# charger.net
KiCad netlist of a schematic drawn in Altium Designer
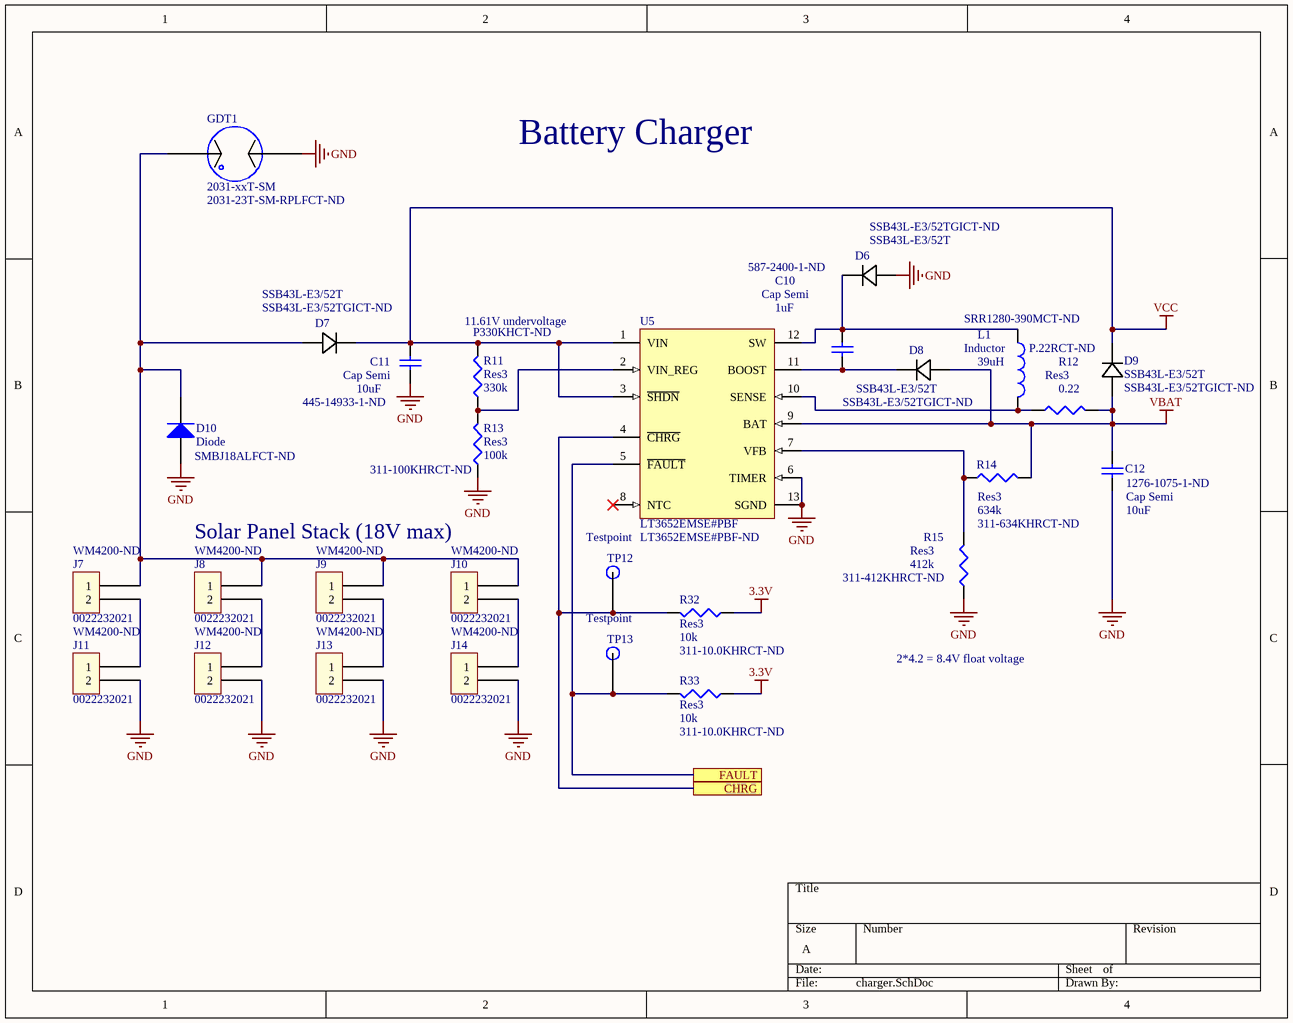
[diagram p0: charger.SchDoc]

(export (version "E")
  (design (tool "Eeschema 10.0.6"))
  (components
    (comp (ref "C10")
      (value "Cap Semi")
      (footprint "1608[0603]")
      (description "Capacitor (Semiconductor SIM Model)")
      (fields
        (field (name "ALTIUM_VALUE") "1uF")
        (field (name "SUPPLIER PART NUMBER 1") "587-2400-1-ND")
        (field (name "MANUFACTURER") "Taiyo Yuden")
        (field (name "MANUFACTURER PART NUMBER") "UMK107BJ105KA-T")
        (field (name "PUBLISHER") "Altium Limited")
      )
      (libsource (lib "Miscellaneous Devices") (part "Cap Semi"))
    )
    (comp (ref "C11")
      (value "Cap Semi")
      (footprint "C1210")
      (description "Capacitor (Semiconductor SIM Model)")
      (fields
        (field (name "ALTIUM_VALUE") "10uF")
        (field (name "SUPPLIER PART NUMBER 1") "445-14933-1-ND")
        (field (name "MANUFACTURER") "TDK")
        (field (name "MANUFACTURER PART NUMBER") "C3225X7R1H106M250AC")
      )
      (libsource (lib "Miscellaneous Devices") (part "Cap Semi"))
    )
    (comp (ref "C12")
      (value "Cap Semi")
      (footprint "C1206")
      (description "Capacitor (Semiconductor SIM Model)")
      (fields
        (field (name "ALTIUM_VALUE") "10uF")
        (field (name "SUPPLIER PART NUMBER 1") "1276-1075-1-ND")
        (field (name "MANUFACTURER") "Samsung")
        (field (name "MANUFACTURER PART NUMBER") "CL31A106KAHNNNE")
        (field (name "PUBLISHER") "Altium Limited")
      )
      (libsource (lib "Miscellaneous Devices") (part "Cap Semi"))
    )
    (comp (ref "D6")
      (value "SSB43L-E3/52T")
      (footprint "DIODE_DO214AA_00")
      (fields
        (field (name "SUPPLIER PART NUMBER 1") "SSB43L-E3/52TGICT-ND")
        (field (name "MANUFACTURER") "Vishay Semiconductors")
      )
      (libsource (lib "vishay") (part "SSB43L-E3/52T"))
    )
    (comp (ref "D7")
      (value "SSB43L-E3/52T")
      (footprint "DIODE_DO214AA_00")
      (fields
        (field (name "SUPPLIER PART NUMBER 1") "SSB43L-E3/52TGICT-ND")
        (field (name "MANUFACTURER") "Vishay Semiconductors")
      )
      (libsource (lib "vishay") (part "SSB43L-E3/52T"))
    )
    (comp (ref "D8")
      (value "SSB43L-E3/52T")
      (footprint "DIODE_DO214AA_00")
      (fields
        (field (name "SUPPLIER PART NUMBER 1") "SSB43L-E3/52TGICT-ND")
        (field (name "MANUFACTURER") "Vishay Semiconductors")
      )
      (libsource (lib "vishay") (part "SSB43L-E3/52T"))
    )
    (comp (ref "D9")
      (value "SSB43L-E3/52T")
      (footprint "DIODE_DO214AA_00")
      (fields
        (field (name "SUPPLIER PART NUMBER 1") "SSB43L-E3/52TGICT-ND")
        (field (name "MANUFACTURER") "Vishay Semiconductors")
      )
      (libsource (lib "vishay") (part "SSB43L-E3/52T"))
    )
    (comp (ref "D10")
      (value "Diode")
      (footprint "smbj")
      (description "Default Diode")
      (fields
        (field (name "SUPPLIER PART NUMBER 1") "SMBJ18ALFCT-ND")
        (field (name "MANUFACTURER") "Littelfuse")
        (field (name "MANUFACTURER PART NUMBER") "SMBJ18A")
      )
      (libsource (lib "Miscellaneous Devices") (part "Diode"))
    )
    (comp (ref "GDT1")
      (value "2031-xxT-SM")
      (footprint "2031-xxT-SM")
      (description "Gas discharge tube")
      (fields
        (field (name "SUPPLIER PART NUMBER 1") "2031-23T-SM-RPLFCT-ND")
        (field (name "MANUFACTURER") "Bourns Inc.")
        (field (name "MANUFACTURER PART NUMBER") "2031-23T-SM-RPLF")
      )
      (libsource (lib "bourns") (part "2031-xxT-SM"))
    )
    (comp (ref "J7")
      (value "0022232021")
      (footprint "0022232021")
      (fields
        (field (name "SUPPLIER PART NUMBER 1") "WM4200-ND")
        (field (name "MANUFACTURER") "Molex")
        (field (name "MANUFACTURER PART NUMBER") "22-23-2021")
      )
      (libsource (lib "molex") (part "0022232021"))
    )
    (comp (ref "J8")
      (value "0022232021")
      (footprint "0022232021")
      (fields
        (field (name "SUPPLIER PART NUMBER 1") "WM4200-ND")
        (field (name "MANUFACTURER") "Molex")
        (field (name "MANUFACTURER PART NUMBER") "22-23-2021")
      )
      (libsource (lib "molex") (part "0022232021"))
    )
    (comp (ref "J9")
      (value "0022232021")
      (footprint "0022232021")
      (fields
        (field (name "SUPPLIER PART NUMBER 1") "WM4200-ND")
        (field (name "MANUFACTURER") "Molex")
        (field (name "MANUFACTURER PART NUMBER") "22-23-2021")
      )
      (libsource (lib "molex") (part "0022232021"))
    )
    (comp (ref "J10")
      (value "0022232021")
      (footprint "0022232021")
      (fields
        (field (name "SUPPLIER PART NUMBER 1") "WM4200-ND")
        (field (name "MANUFACTURER") "Molex")
        (field (name "MANUFACTURER PART NUMBER") "22-23-2021")
      )
      (libsource (lib "molex") (part "0022232021"))
    )
    (comp (ref "J11")
      (value "0022232021")
      (footprint "0022232021")
      (fields
        (field (name "SUPPLIER PART NUMBER 1") "WM4200-ND")
        (field (name "MANUFACTURER") "Molex")
        (field (name "MANUFACTURER PART NUMBER") "22-23-2021")
      )
      (libsource (lib "molex") (part "0022232021"))
    )
    (comp (ref "J12")
      (value "0022232021")
      (footprint "0022232021")
      (fields
        (field (name "SUPPLIER PART NUMBER 1") "WM4200-ND")
        (field (name "MANUFACTURER") "Molex")
        (field (name "MANUFACTURER PART NUMBER") "22-23-2021")
      )
      (libsource (lib "molex") (part "0022232021"))
    )
    (comp (ref "J13")
      (value "0022232021")
      (footprint "0022232021")
      (fields
        (field (name "SUPPLIER PART NUMBER 1") "WM4200-ND")
        (field (name "MANUFACTURER") "Molex")
        (field (name "MANUFACTURER PART NUMBER") "22-23-2021")
      )
      (libsource (lib "molex") (part "0022232021"))
    )
    (comp (ref "J14")
      (value "0022232021")
      (footprint "0022232021")
      (fields
        (field (name "SUPPLIER PART NUMBER 1") "WM4200-ND")
        (field (name "MANUFACTURER") "Molex")
        (field (name "MANUFACTURER PART NUMBER") "22-23-2021")
      )
      (libsource (lib "molex") (part "0022232021"))
    )
    (comp (ref "L1")
      (value "Inductor")
      (footprint "SRR1280-390M")
      (fields
        (field (name "ALTIUM_VALUE") "39uH")
        (field (name "SUPPLIER PART NUMBER 1") "SRR1280-390MCT-ND")
        (field (name "MANUFACTURER") "Bourns")
        (field (name "MANUFACTURER PART NUMBER") "SRR1280-390M")
        (field (name "TOLERANCE") "20%")
        (field (name "PUBLISHER") "Altium Limited")
      )
      (libsource (lib "Miscellaneous Devices") (part "Inductor"))
    )
    (comp (ref "R11")
      (value "Res3")
      (footprint "J1-0603")
      (description "Resistor")
      (fields
        (field (name "ALTIUM_VALUE") "330k")
        (field (name "SUPPLIER PART NUMBER 1") "P330KHCT-ND")
        (field (name "MANUFACTURER") "Panasonic")
        (field (name "MANUFACTURER PART NUMBER") "ERJ-3EKF3303V")
        (field (name "PUBLISHER") "Altium Limited")
      )
      (libsource (lib "Miscellaneous Devices") (part "Res3"))
    )
    (comp (ref "R12")
      (value "Res3")
      (footprint "RESC1206")
      (description "Resistor")
      (fields
        (field (name "ALTIUM_VALUE") "0.22")
        (field (name "SUPPLIER PART NUMBER 1") "P.22RCT-ND")
        (field (name "MANUFACTURER") "Panasonic")
        (field (name "MANUFACTURER PART NUMBER") "ERJ-8RQFR22V")
        (field (name "PUBLISHER") "Altium Limited")
      )
      (libsource (lib "Miscellaneous Devices") (part "Res3"))
    )
    (comp (ref "R13")
      (value "Res3")
      (footprint "J1-0603")
      (description "Resistor")
      (fields
        (field (name "ALTIUM_VALUE") "100k")
        (field (name "SUPPLIER PART NUMBER 1") "311-100KHRCT-ND")
        (field (name "MANUFACTURER") "Yageo")
        (field (name "MANUFACTURER PART NUMBER") "RC0603FR-07100KL")
        (field (name "PUBLISHER") "Altium Limited")
      )
      (libsource (lib "Miscellaneous Devices") (part "Res3"))
    )
    (comp (ref "R14")
      (value "Res3")
      (footprint "J1-0603")
      (description "Resistor")
      (fields
        (field (name "ALTIUM_VALUE") "634k")
        (field (name "SUPPLIER PART NUMBER 1") "311-634KHRCT-ND")
        (field (name "MANUFACTURER") "Yageo")
        (field (name "MANUFACTURER PART NUMBER") "RC0603FR-07634KL")
        (field (name "PUBLISHER") "Altium Limited")
      )
      (libsource (lib "Miscellaneous Devices") (part "Res3"))
    )
    (comp (ref "R15")
      (value "Res3")
      (footprint "J1-0603")
      (description "Resistor")
      (fields
        (field (name "ALTIUM_VALUE") "412k")
        (field (name "SUPPLIER PART NUMBER 1") "311-412KHRCT-ND")
        (field (name "MANUFACTURER") "Yageo")
        (field (name "MANUFACTURER PART NUMBER") "RC0603FR-07412KL")
        (field (name "PUBLISHER") "Altium Limited")
      )
      (libsource (lib "Miscellaneous Devices") (part "Res3"))
    )
    (comp (ref "R32")
      (value "Res3")
      (footprint "J1-0603")
      (description "Resistor")
      (fields
        (field (name "ALTIUM_VALUE") "10k")
        (field (name "SUPPLIER PART NUMBER 1") "311-10.0KHRCT-ND")
        (field (name "MANUFACTURER") "Yageo")
        (field (name "MANUFACTURER PART NUMBER") "RC0603FR-0710KL")
        (field (name "PUBLISHER") "Altium Limited")
      )
      (libsource (lib "Miscellaneous Devices") (part "Res3"))
    )
    (comp (ref "R33")
      (value "Res3")
      (footprint "J1-0603")
      (description "Resistor")
      (fields
        (field (name "ALTIUM_VALUE") "10k")
        (field (name "SUPPLIER PART NUMBER 1") "311-10.0KHRCT-ND")
        (field (name "MANUFACTURER") "Yageo")
        (field (name "MANUFACTURER PART NUMBER") "RC0603FR-0710KL")
        (field (name "PUBLISHER") "Altium Limited")
      )
      (libsource (lib "Miscellaneous Devices") (part "Res3"))
    )
    (comp (ref "TP12")
      (value "Testpoint")
      (footprint "testpoint")
      (description "SMT Testpoint")
      (libsource (lib "testpoints") (part "SMT Testpoint"))
    )
    (comp (ref "TP13")
      (value "Testpoint")
      (footprint "testpoint")
      (description "SMT Testpoint")
      (libsource (lib "testpoints") (part "SMT Testpoint"))
    )
    (comp (ref "U5")
      (value "LT3652EMSE#PBF")
      (footprint "LT-MSE-12-EDP_M")
      (fields
        (field (name "MANUFACTURER") "Linear Technology")
        (field (name "SUPPLIER PART NUMBER 1") "LT3652EMSE#PBF-ND")
      )
      (libsource (lib "Altium Content Vault") (part "LT-LT3652-MSE-12_3652HV-DD-12"))
    )
  )
  (nets
    (net (code "1") (name "/CHRG") (class "Default")
      (node (ref "R32") (pin "2") (pinfunction "2_2") (pintype "passive"))
      (node (ref "TP12") (pin "1") (pinfunction "1_1") (pintype "passive"))
      (node (ref "U5") (pin "4") (pinfunction "~{CHRG}_4") (pintype "tri_state"))
    )
    (net (code "2") (name "/FAULT") (class "Default")
      (node (ref "R33") (pin "2") (pinfunction "2_2") (pintype "passive"))
      (node (ref "TP13") (pin "1") (pinfunction "1_1") (pintype "passive"))
      (node (ref "U5") (pin "5") (pinfunction "~{FAULT}_5") (pintype "tri_state"))
    )
    (net (code "3") (name "3.3V") (class "Default")
      (node (ref "R32") (pin "1") (pinfunction "1_1") (pintype "passive"))
      (node (ref "R33") (pin "1") (pinfunction "1_1") (pintype "passive"))
    )
    (net (code "4") (name "GND") (class "Default")
      (node (ref "C11") (pin "1") (pinfunction "1_1") (pintype "passive"))
      (node (ref "C12") (pin "1") (pinfunction "1_1") (pintype "passive"))
      (node (ref "D10") (pin "1") (pinfunction "A_1") (pintype "passive"))
      (node (ref "D6") (pin "2") (pinfunction "2_2") (pintype "passive"))
      (node (ref "GDT1") (pin "1") (pinfunction "1_1") (pintype "passive"))
      (node (ref "J11") (pin "2") (pinfunction "2_2") (pintype "passive"))
      (node (ref "J12") (pin "2") (pinfunction "2_2") (pintype "passive"))
      (node (ref "J13") (pin "2") (pinfunction "2_2") (pintype "passive"))
      (node (ref "J14") (pin "2") (pinfunction "2_2") (pintype "passive"))
      (node (ref "R13") (pin "1") (pinfunction "1_1") (pintype "passive"))
      (node (ref "R15") (pin "1") (pinfunction "1_1") (pintype "passive"))
      (node (ref "U5") (pin "13") (pinfunction "SGND_13") (pintype "power_in"))
      (node (ref "U5") (pin "6") (pinfunction "TIMER_6") (pintype "input"))
    )
    (net (code "5") (name "Net-(D10-K)") (class "Default")
      (node (ref "D10") (pin "2") (pinfunction "K_2") (pintype "passive"))
      (node (ref "D7") (pin "2") (pinfunction "2_2") (pintype "passive"))
      (node (ref "GDT1") (pin "2") (pinfunction "2_2") (pintype "passive"))
      (node (ref "J10") (pin "1") (pinfunction "1_1") (pintype "passive"))
      (node (ref "J7") (pin "1") (pinfunction "1_1") (pintype "passive"))
      (node (ref "J8") (pin "1") (pinfunction "1_1") (pintype "passive"))
      (node (ref "J9") (pin "1") (pinfunction "1_1") (pintype "passive"))
    )
    (net (code "6") (name "Net-(J10-Pad2)") (class "Default")
      (node (ref "J10") (pin "2") (pinfunction "2_2") (pintype "passive"))
      (node (ref "J14") (pin "1") (pinfunction "1_1") (pintype "passive"))
    )
    (net (code "7") (name "Net-(J11-Pad1)") (class "Default")
      (node (ref "J11") (pin "1") (pinfunction "1_1") (pintype "passive"))
      (node (ref "J7") (pin "2") (pinfunction "2_2") (pintype "passive"))
    )
    (net (code "8") (name "Net-(J12-Pad1)") (class "Default")
      (node (ref "J12") (pin "1") (pinfunction "1_1") (pintype "passive"))
      (node (ref "J8") (pin "2") (pinfunction "2_2") (pintype "passive"))
    )
    (net (code "9") (name "Net-(J13-Pad1)") (class "Default")
      (node (ref "J13") (pin "1") (pinfunction "1_1") (pintype "passive"))
      (node (ref "J9") (pin "2") (pinfunction "2_2") (pintype "passive"))
    )
    (net (code "10") (name "Net-(U5-BOOST)") (class "Default")
      (node (ref "C10") (pin "1") (pinfunction "1_1") (pintype "passive"))
      (node (ref "D8") (pin "1") (pinfunction "1_1") (pintype "passive"))
      (node (ref "U5") (pin "11") (pinfunction "BOOST_11") (pintype "power_in"))
    )
    (net (code "11") (name "Net-(U5-SENSE)") (class "Default")
      (node (ref "L1") (pin "2") (pinfunction "2_2") (pintype "passive"))
      (node (ref "R12") (pin "1") (pinfunction "1_1") (pintype "passive"))
      (node (ref "U5") (pin "10") (pinfunction "SENSE_10") (pintype "input"))
    )
    (net (code "12") (name "Net-(U5-SW)") (class "Default")
      (node (ref "C10") (pin "2") (pinfunction "2_2") (pintype "passive"))
      (node (ref "D6") (pin "1") (pinfunction "1_1") (pintype "passive"))
      (node (ref "L1") (pin "1") (pinfunction "1_1") (pintype "passive"))
      (node (ref "U5") (pin "12") (pinfunction "SW_12") (pintype "power_in"))
    )
    (net (code "13") (name "Net-(U5-VFB)") (class "Default")
      (node (ref "R14") (pin "1") (pinfunction "1_1") (pintype "passive"))
      (node (ref "R15") (pin "2") (pinfunction "2_2") (pintype "passive"))
      (node (ref "U5") (pin "7") (pinfunction "VFB_7") (pintype "input"))
    )
    (net (code "14") (name "Net-(U5-VIN_REG)") (class "Default")
      (node (ref "R11") (pin "1") (pinfunction "1_1") (pintype "passive"))
      (node (ref "R13") (pin "2") (pinfunction "2_2") (pintype "passive"))
      (node (ref "U5") (pin "2") (pinfunction "VIN_REG_2") (pintype "input"))
    )
    (net (code "15") (name "VBAT") (class "Default")
      (node (ref "C12") (pin "2") (pinfunction "2_2") (pintype "passive"))
      (node (ref "D8") (pin "2") (pinfunction "2_2") (pintype "passive"))
      (node (ref "D9") (pin "2") (pinfunction "2_2") (pintype "passive"))
      (node (ref "R12") (pin "2") (pinfunction "2_2") (pintype "passive"))
      (node (ref "R14") (pin "2") (pinfunction "2_2") (pintype "passive"))
      (node (ref "U5") (pin "9") (pinfunction "BAT_9") (pintype "input"))
    )
    (net (code "16") (name "VCC") (class "Default")
      (node (ref "C11") (pin "2") (pinfunction "2_2") (pintype "passive"))
      (node (ref "D7") (pin "1") (pinfunction "1_1") (pintype "passive"))
      (node (ref "D9") (pin "1") (pinfunction "1_1") (pintype "passive"))
      (node (ref "R11") (pin "2") (pinfunction "2_2") (pintype "passive"))
      (node (ref "U5") (pin "1") (pinfunction "VIN_1") (pintype "power_in"))
      (node (ref "U5") (pin "3") (pinfunction "~{SHDN}_3") (pintype "input"))
    )
    (net (code "17") (name "unconnected-(U5-NTC-Pad8)") (class "Default")
      (node (ref "U5") (pin "8") (pinfunction "NTC_8") (pintype "input+no_connect"))
    )
  )
)
